# FPGA_LVDS.net
KiCad netlist of a schematic drawn in Altium Designer
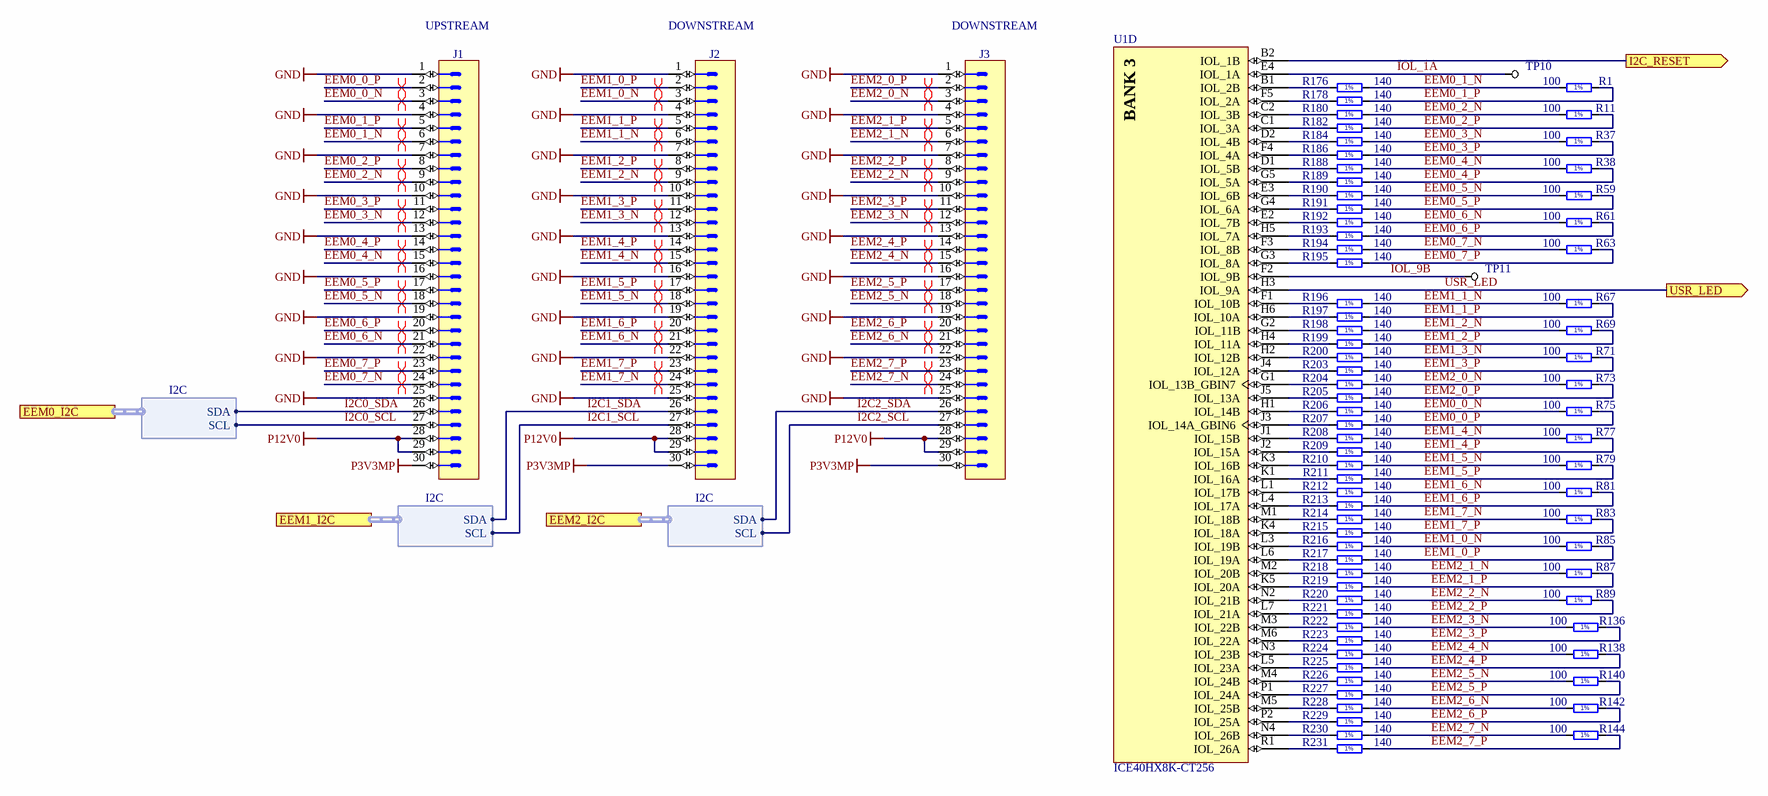
[diagram p0: FPGA_LVDS.SchDoc]

(export (version "E")
  (design (tool "Eeschema 10.0.6"))
  (components
    (comp (ref "J1")
      (value "~")
      (footprint "3M_N2530-6002RB")
      (description "Connector 30 Male")
      (fields
        (field (name "PART NUMBER") "3M_N2530-6002RB")
        (field (name "MANUFACTURER") "3M")
        (field (name "AUTHOR") "CERN DEM JLC")
      )
      (libsource (lib "Connectors") (part "Connector 30 Male"))
    )
    (comp (ref "J2")
      (value "~")
      (footprint "3M_N2530-6002RB")
      (description "Connector 30 Male")
      (fields
        (field (name "PART NUMBER") "3M_N2530-6002RB")
        (field (name "MANUFACTURER") "3M")
        (field (name "AUTHOR") "CERN DEM JLC")
      )
      (libsource (lib "Connectors") (part "Connector 30 Male"))
    )
    (comp (ref "J3")
      (value "~")
      (footprint "3M_N2530-6002RB")
      (description "Connector 30 Male")
      (fields
        (field (name "PART NUMBER") "3M_N2530-6002RB")
        (field (name "MANUFACTURER") "3M")
        (field (name "AUTHOR") "CERN DEM JLC")
      )
      (libsource (lib "Connectors") (part "Connector 30 Male"))
    )
    (comp (ref "R1")
      (value "100")
      (footprint "RESC1005X40N")
      (description "Resistor - 1%")
      (fields
        (field (name "PART NUMBER") "R0402_100R_1%_0.0625W_100PPM")
        (field (name "POWER") "0.0625W")
        (field (name "AUTHOR") "CERN DEM JLC")
      )
      (libsource (lib "Resistors") (part "Resistor - 1%"))
    )
    (comp (ref "R11")
      (value "100")
      (footprint "RESC1005X40N")
      (description "Resistor - 1%")
      (fields
        (field (name "PART NUMBER") "R0402_100R_1%_0.0625W_100PPM")
        (field (name "POWER") "0.0625W")
        (field (name "AUTHOR") "CERN DEM JLC")
      )
      (libsource (lib "Resistors") (part "Resistor - 1%"))
    )
    (comp (ref "R37")
      (value "100")
      (footprint "RESC1005X40N")
      (description "Resistor - 1%")
      (fields
        (field (name "PART NUMBER") "R0402_100R_1%_0.0625W_100PPM")
        (field (name "POWER") "0.0625W")
        (field (name "AUTHOR") "CERN DEM JLC")
      )
      (libsource (lib "Resistors") (part "Resistor - 1%"))
    )
    (comp (ref "R38")
      (value "100")
      (footprint "RESC1005X40N")
      (description "Resistor - 1%")
      (fields
        (field (name "PART NUMBER") "R0402_100R_1%_0.0625W_100PPM")
        (field (name "POWER") "0.0625W")
        (field (name "AUTHOR") "CERN DEM JLC")
      )
      (libsource (lib "Resistors") (part "Resistor - 1%"))
    )
    (comp (ref "R59")
      (value "100")
      (footprint "RESC1005X40N")
      (description "Resistor - 1%")
      (fields
        (field (name "PART NUMBER") "R0402_100R_1%_0.0625W_100PPM")
        (field (name "POWER") "0.0625W")
        (field (name "AUTHOR") "CERN DEM JLC")
      )
      (libsource (lib "Resistors") (part "Resistor - 1%"))
    )
    (comp (ref "R61")
      (value "100")
      (footprint "RESC1005X40N")
      (description "Resistor - 1%")
      (fields
        (field (name "PART NUMBER") "R0402_100R_1%_0.0625W_100PPM")
        (field (name "POWER") "0.0625W")
        (field (name "AUTHOR") "CERN DEM JLC")
      )
      (libsource (lib "Resistors") (part "Resistor - 1%"))
    )
    (comp (ref "R63")
      (value "100")
      (footprint "RESC1005X40N")
      (description "Resistor - 1%")
      (fields
        (field (name "PART NUMBER") "R0402_100R_1%_0.0625W_100PPM")
        (field (name "POWER") "0.0625W")
        (field (name "AUTHOR") "CERN DEM JLC")
      )
      (libsource (lib "Resistors") (part "Resistor - 1%"))
    )
    (comp (ref "R67")
      (value "100")
      (footprint "RESC1005X40N")
      (description "Resistor - 1%")
      (fields
        (field (name "PART NUMBER") "R0402_100R_1%_0.0625W_100PPM")
        (field (name "POWER") "0.0625W")
        (field (name "AUTHOR") "CERN DEM JLC")
      )
      (libsource (lib "Resistors") (part "Resistor - 1%"))
    )
    (comp (ref "R69")
      (value "100")
      (footprint "RESC1005X40N")
      (description "Resistor - 1%")
      (fields
        (field (name "PART NUMBER") "R0402_100R_1%_0.0625W_100PPM")
        (field (name "POWER") "0.0625W")
        (field (name "AUTHOR") "CERN DEM JLC")
      )
      (libsource (lib "Resistors") (part "Resistor - 1%"))
    )
    (comp (ref "R71")
      (value "100")
      (footprint "RESC1005X40N")
      (description "Resistor - 1%")
      (fields
        (field (name "PART NUMBER") "R0402_100R_1%_0.0625W_100PPM")
        (field (name "POWER") "0.0625W")
        (field (name "AUTHOR") "CERN DEM JLC")
      )
      (libsource (lib "Resistors") (part "Resistor - 1%"))
    )
    (comp (ref "R73")
      (value "100")
      (footprint "RESC1005X40N")
      (description "Resistor - 1%")
      (fields
        (field (name "PART NUMBER") "R0402_100R_1%_0.0625W_100PPM")
        (field (name "POWER") "0.0625W")
        (field (name "AUTHOR") "CERN DEM JLC")
      )
      (libsource (lib "Resistors") (part "Resistor - 1%"))
    )
    (comp (ref "R75")
      (value "100")
      (footprint "RESC1005X40N")
      (description "Resistor - 1%")
      (fields
        (field (name "PART NUMBER") "R0402_100R_1%_0.0625W_100PPM")
        (field (name "POWER") "0.0625W")
        (field (name "AUTHOR") "CERN DEM JLC")
      )
      (libsource (lib "Resistors") (part "Resistor - 1%"))
    )
    (comp (ref "R77")
      (value "100")
      (footprint "RESC1005X40N")
      (description "Resistor - 1%")
      (fields
        (field (name "PART NUMBER") "R0402_100R_1%_0.0625W_100PPM")
        (field (name "POWER") "0.0625W")
        (field (name "AUTHOR") "CERN DEM JLC")
      )
      (libsource (lib "Resistors") (part "Resistor - 1%"))
    )
    (comp (ref "R79")
      (value "100")
      (footprint "RESC1005X40N")
      (description "Resistor - 1%")
      (fields
        (field (name "PART NUMBER") "R0402_100R_1%_0.0625W_100PPM")
        (field (name "POWER") "0.0625W")
        (field (name "AUTHOR") "CERN DEM JLC")
      )
      (libsource (lib "Resistors") (part "Resistor - 1%"))
    )
    (comp (ref "R81")
      (value "100")
      (footprint "RESC1005X40N")
      (description "Resistor - 1%")
      (fields
        (field (name "PART NUMBER") "R0402_100R_1%_0.0625W_100PPM")
        (field (name "POWER") "0.0625W")
        (field (name "AUTHOR") "CERN DEM JLC")
      )
      (libsource (lib "Resistors") (part "Resistor - 1%"))
    )
    (comp (ref "R83")
      (value "100")
      (footprint "RESC1005X40N")
      (description "Resistor - 1%")
      (fields
        (field (name "PART NUMBER") "R0402_100R_1%_0.0625W_100PPM")
        (field (name "POWER") "0.0625W")
        (field (name "AUTHOR") "CERN DEM JLC")
      )
      (libsource (lib "Resistors") (part "Resistor - 1%"))
    )
    (comp (ref "R85")
      (value "100")
      (footprint "RESC1005X40N")
      (description "Resistor - 1%")
      (fields
        (field (name "PART NUMBER") "R0402_100R_1%_0.0625W_100PPM")
        (field (name "POWER") "0.0625W")
        (field (name "AUTHOR") "CERN DEM JLC")
      )
      (libsource (lib "Resistors") (part "Resistor - 1%"))
    )
    (comp (ref "R87")
      (value "100")
      (footprint "RESC1005X40N")
      (description "Resistor - 1%")
      (fields
        (field (name "PART NUMBER") "R0402_100R_1%_0.0625W_100PPM")
        (field (name "POWER") "0.0625W")
        (field (name "AUTHOR") "CERN DEM JLC")
      )
      (libsource (lib "Resistors") (part "Resistor - 1%"))
    )
    (comp (ref "R89")
      (value "100")
      (footprint "RESC1005X40N")
      (description "Resistor - 1%")
      (fields
        (field (name "PART NUMBER") "R0402_100R_1%_0.0625W_100PPM")
        (field (name "POWER") "0.0625W")
        (field (name "AUTHOR") "CERN DEM JLC")
      )
      (libsource (lib "Resistors") (part "Resistor - 1%"))
    )
    (comp (ref "R136")
      (value "100")
      (footprint "RESC1005X40N")
      (description "Resistor - 1%")
      (fields
        (field (name "PART NUMBER") "R0402_100R_1%_0.0625W_100PPM")
        (field (name "POWER") "0.0625W")
        (field (name "AUTHOR") "CERN DEM JLC")
      )
      (libsource (lib "Resistors") (part "Resistor - 1%"))
    )
    (comp (ref "R138")
      (value "100")
      (footprint "RESC1005X40N")
      (description "Resistor - 1%")
      (fields
        (field (name "PART NUMBER") "R0402_100R_1%_0.0625W_100PPM")
        (field (name "POWER") "0.0625W")
        (field (name "AUTHOR") "CERN DEM JLC")
      )
      (libsource (lib "Resistors") (part "Resistor - 1%"))
    )
    (comp (ref "R140")
      (value "100")
      (footprint "RESC1005X40N")
      (description "Resistor - 1%")
      (fields
        (field (name "PART NUMBER") "R0402_100R_1%_0.0625W_100PPM")
        (field (name "POWER") "0.0625W")
        (field (name "AUTHOR") "CERN DEM JLC")
      )
      (libsource (lib "Resistors") (part "Resistor - 1%"))
    )
    (comp (ref "R142")
      (value "100")
      (footprint "RESC1005X40N")
      (description "Resistor - 1%")
      (fields
        (field (name "PART NUMBER") "R0402_100R_1%_0.0625W_100PPM")
        (field (name "POWER") "0.0625W")
        (field (name "AUTHOR") "CERN DEM JLC")
      )
      (libsource (lib "Resistors") (part "Resistor - 1%"))
    )
    (comp (ref "R144")
      (value "100")
      (footprint "RESC1005X40N")
      (description "Resistor - 1%")
      (fields
        (field (name "PART NUMBER") "R0402_100R_1%_0.0625W_100PPM")
        (field (name "POWER") "0.0625W")
        (field (name "AUTHOR") "CERN DEM JLC")
      )
      (libsource (lib "Resistors") (part "Resistor - 1%"))
    )
    (comp (ref "R176")
      (value "140")
      (footprint "RESC0603X28N")
      (description "Resistor - 1%")
      (fields
        (field (name "PART NUMBER") "R0201_140R_1%_0.05W_200PPM")
        (field (name "POWER") "0.05W")
        (field (name "AUTHOR") "CERN DEM MR")
      )
      (libsource (lib "Resistors") (part "Resistor - 1%"))
    )
    (comp (ref "R178")
      (value "140")
      (footprint "RESC0603X28N")
      (description "Resistor - 1%")
      (fields
        (field (name "PART NUMBER") "R0201_140R_1%_0.05W_200PPM")
        (field (name "POWER") "0.05W")
        (field (name "AUTHOR") "CERN DEM MR")
      )
      (libsource (lib "Resistors") (part "Resistor - 1%"))
    )
    (comp (ref "R180")
      (value "140")
      (footprint "RESC0603X28N")
      (description "Resistor - 1%")
      (fields
        (field (name "PART NUMBER") "R0201_140R_1%_0.05W_200PPM")
        (field (name "POWER") "0.05W")
        (field (name "AUTHOR") "CERN DEM MR")
      )
      (libsource (lib "Resistors") (part "Resistor - 1%"))
    )
    (comp (ref "R182")
      (value "140")
      (footprint "RESC0603X28N")
      (description "Resistor - 1%")
      (fields
        (field (name "PART NUMBER") "R0201_140R_1%_0.05W_200PPM")
        (field (name "POWER") "0.05W")
        (field (name "AUTHOR") "CERN DEM MR")
      )
      (libsource (lib "Resistors") (part "Resistor - 1%"))
    )
    (comp (ref "R184")
      (value "140")
      (footprint "RESC0603X28N")
      (description "Resistor - 1%")
      (fields
        (field (name "PART NUMBER") "R0201_140R_1%_0.05W_200PPM")
        (field (name "POWER") "0.05W")
        (field (name "AUTHOR") "CERN DEM MR")
      )
      (libsource (lib "Resistors") (part "Resistor - 1%"))
    )
    (comp (ref "R186")
      (value "140")
      (footprint "RESC0603X28N")
      (description "Resistor - 1%")
      (fields
        (field (name "PART NUMBER") "R0201_140R_1%_0.05W_200PPM")
        (field (name "POWER") "0.05W")
        (field (name "AUTHOR") "CERN DEM MR")
      )
      (libsource (lib "Resistors") (part "Resistor - 1%"))
    )
    (comp (ref "R188")
      (value "140")
      (footprint "RESC0603X28N")
      (description "Resistor - 1%")
      (fields
        (field (name "PART NUMBER") "R0201_140R_1%_0.05W_200PPM")
        (field (name "POWER") "0.05W")
        (field (name "AUTHOR") "CERN DEM MR")
      )
      (libsource (lib "Resistors") (part "Resistor - 1%"))
    )
    (comp (ref "R189")
      (value "140")
      (footprint "RESC0603X28N")
      (description "Resistor - 1%")
      (fields
        (field (name "PART NUMBER") "R0201_140R_1%_0.05W_200PPM")
        (field (name "POWER") "0.05W")
        (field (name "AUTHOR") "CERN DEM MR")
      )
      (libsource (lib "Resistors") (part "Resistor - 1%"))
    )
    (comp (ref "R190")
      (value "140")
      (footprint "RESC0603X28N")
      (description "Resistor - 1%")
      (fields
        (field (name "PART NUMBER") "R0201_140R_1%_0.05W_200PPM")
        (field (name "POWER") "0.05W")
        (field (name "AUTHOR") "CERN DEM MR")
      )
      (libsource (lib "Resistors") (part "Resistor - 1%"))
    )
    (comp (ref "R191")
      (value "140")
      (footprint "RESC0603X28N")
      (description "Resistor - 1%")
      (fields
        (field (name "PART NUMBER") "R0201_140R_1%_0.05W_200PPM")
        (field (name "POWER") "0.05W")
        (field (name "AUTHOR") "CERN DEM MR")
      )
      (libsource (lib "Resistors") (part "Resistor - 1%"))
    )
    (comp (ref "R192")
      (value "140")
      (footprint "RESC0603X28N")
      (description "Resistor - 1%")
      (fields
        (field (name "PART NUMBER") "R0201_140R_1%_0.05W_200PPM")
        (field (name "POWER") "0.05W")
        (field (name "AUTHOR") "CERN DEM MR")
      )
      (libsource (lib "Resistors") (part "Resistor - 1%"))
    )
    (comp (ref "R193")
      (value "140")
      (footprint "RESC0603X28N")
      (description "Resistor - 1%")
      (fields
        (field (name "PART NUMBER") "R0201_140R_1%_0.05W_200PPM")
        (field (name "POWER") "0.05W")
        (field (name "AUTHOR") "CERN DEM MR")
      )
      (libsource (lib "Resistors") (part "Resistor - 1%"))
    )
    (comp (ref "R194")
      (value "140")
      (footprint "RESC0603X28N")
      (description "Resistor - 1%")
      (fields
        (field (name "PART NUMBER") "R0201_140R_1%_0.05W_200PPM")
        (field (name "POWER") "0.05W")
        (field (name "AUTHOR") "CERN DEM MR")
      )
      (libsource (lib "Resistors") (part "Resistor - 1%"))
    )
    (comp (ref "R195")
      (value "140")
      (footprint "RESC0603X28N")
      (description "Resistor - 1%")
      (fields
        (field (name "PART NUMBER") "R0201_140R_1%_0.05W_200PPM")
        (field (name "POWER") "0.05W")
        (field (name "AUTHOR") "CERN DEM MR")
      )
      (libsource (lib "Resistors") (part "Resistor - 1%"))
    )
    (comp (ref "R196")
      (value "140")
      (footprint "RESC0603X28N")
      (description "Resistor - 1%")
      (fields
        (field (name "PART NUMBER") "R0201_140R_1%_0.05W_200PPM")
        (field (name "POWER") "0.05W")
        (field (name "AUTHOR") "CERN DEM MR")
      )
      (libsource (lib "Resistors") (part "Resistor - 1%"))
    )
    (comp (ref "R197")
      (value "140")
      (footprint "RESC0603X28N")
      (description "Resistor - 1%")
      (fields
        (field (name "PART NUMBER") "R0201_140R_1%_0.05W_200PPM")
        (field (name "POWER") "0.05W")
        (field (name "AUTHOR") "CERN DEM MR")
      )
      (libsource (lib "Resistors") (part "Resistor - 1%"))
    )
    (comp (ref "R198")
      (value "140")
      (footprint "RESC0603X28N")
      (description "Resistor - 1%")
      (fields
        (field (name "PART NUMBER") "R0201_140R_1%_0.05W_200PPM")
        (field (name "POWER") "0.05W")
        (field (name "AUTHOR") "CERN DEM MR")
      )
      (libsource (lib "Resistors") (part "Resistor - 1%"))
    )
    (comp (ref "R199")
      (value "140")
      (footprint "RESC0603X28N")
      (description "Resistor - 1%")
      (fields
        (field (name "PART NUMBER") "R0201_140R_1%_0.05W_200PPM")
        (field (name "POWER") "0.05W")
        (field (name "AUTHOR") "CERN DEM MR")
      )
      (libsource (lib "Resistors") (part "Resistor - 1%"))
    )
    (comp (ref "R200")
      (value "140")
      (footprint "RESC0603X28N")
      (description "Resistor - 1%")
      (fields
        (field (name "PART NUMBER") "R0201_140R_1%_0.05W_200PPM")
        (field (name "POWER") "0.05W")
        (field (name "AUTHOR") "CERN DEM MR")
      )
      (libsource (lib "Resistors") (part "Resistor - 1%"))
    )
    (comp (ref "R203")
      (value "140")
      (footprint "RESC0603X28N")
      (description "Resistor - 1%")
      (fields
        (field (name "PART NUMBER") "R0201_140R_1%_0.05W_200PPM")
        (field (name "POWER") "0.05W")
        (field (name "AUTHOR") "CERN DEM MR")
      )
      (libsource (lib "Resistors") (part "Resistor - 1%"))
    )
    (comp (ref "R204")
      (value "140")
      (footprint "RESC0603X28N")
      (description "Resistor - 1%")
      (fields
        (field (name "PART NUMBER") "R0201_140R_1%_0.05W_200PPM")
        (field (name "POWER") "0.05W")
        (field (name "AUTHOR") "CERN DEM MR")
      )
      (libsource (lib "Resistors") (part "Resistor - 1%"))
    )
    (comp (ref "R205")
      (value "140")
      (footprint "RESC0603X28N")
      (description "Resistor - 1%")
      (fields
        (field (name "PART NUMBER") "R0201_140R_1%_0.05W_200PPM")
        (field (name "POWER") "0.05W")
        (field (name "AUTHOR") "CERN DEM MR")
      )
      (libsource (lib "Resistors") (part "Resistor - 1%"))
    )
    (comp (ref "R206")
      (value "140")
      (footprint "RESC0603X28N")
      (description "Resistor - 1%")
      (fields
        (field (name "PART NUMBER") "R0201_140R_1%_0.05W_200PPM")
        (field (name "POWER") "0.05W")
        (field (name "AUTHOR") "CERN DEM MR")
      )
      (libsource (lib "Resistors") (part "Resistor - 1%"))
    )
    (comp (ref "R207")
      (value "140")
      (footprint "RESC0603X28N")
      (description "Resistor - 1%")
      (fields
        (field (name "PART NUMBER") "R0201_140R_1%_0.05W_200PPM")
        (field (name "POWER") "0.05W")
        (field (name "AUTHOR") "CERN DEM MR")
      )
      (libsource (lib "Resistors") (part "Resistor - 1%"))
    )
    (comp (ref "R208")
      (value "140")
      (footprint "RESC0603X28N")
      (description "Resistor - 1%")
      (fields
        (field (name "PART NUMBER") "R0201_140R_1%_0.05W_200PPM")
        (field (name "POWER") "0.05W")
        (field (name "AUTHOR") "CERN DEM MR")
      )
      (libsource (lib "Resistors") (part "Resistor - 1%"))
    )
    (comp (ref "R209")
      (value "140")
      (footprint "RESC0603X28N")
      (description "Resistor - 1%")
      (fields
        (field (name "PART NUMBER") "R0201_140R_1%_0.05W_200PPM")
        (field (name "POWER") "0.05W")
        (field (name "AUTHOR") "CERN DEM MR")
      )
      (libsource (lib "Resistors") (part "Resistor - 1%"))
    )
    (comp (ref "R210")
      (value "140")
      (footprint "RESC0603X28N")
      (description "Resistor - 1%")
      (fields
        (field (name "PART NUMBER") "R0201_140R_1%_0.05W_200PPM")
        (field (name "POWER") "0.05W")
        (field (name "AUTHOR") "CERN DEM MR")
      )
      (libsource (lib "Resistors") (part "Resistor - 1%"))
    )
    (comp (ref "R211")
      (value "140")
      (footprint "RESC0603X28N")
      (description "Resistor - 1%")
      (fields
        (field (name "PART NUMBER") "R0201_140R_1%_0.05W_200PPM")
        (field (name "POWER") "0.05W")
        (field (name "AUTHOR") "CERN DEM MR")
      )
      (libsource (lib "Resistors") (part "Resistor - 1%"))
    )
    (comp (ref "R212")
      (value "140")
      (footprint "RESC0603X28N")
      (description "Resistor - 1%")
      (fields
        (field (name "PART NUMBER") "R0201_140R_1%_0.05W_200PPM")
        (field (name "POWER") "0.05W")
        (field (name "AUTHOR") "CERN DEM MR")
      )
      (libsource (lib "Resistors") (part "Resistor - 1%"))
    )
    (comp (ref "R213")
      (value "140")
      (footprint "RESC0603X28N")
      (description "Resistor - 1%")
      (fields
        (field (name "PART NUMBER") "R0201_140R_1%_0.05W_200PPM")
        (field (name "POWER") "0.05W")
        (field (name "AUTHOR") "CERN DEM MR")
      )
      (libsource (lib "Resistors") (part "Resistor - 1%"))
    )
    (comp (ref "R214")
      (value "140")
      (footprint "RESC0603X28N")
      (description "Resistor - 1%")
      (fields
        (field (name "PART NUMBER") "R0201_140R_1%_0.05W_200PPM")
        (field (name "POWER") "0.05W")
        (field (name "AUTHOR") "CERN DEM MR")
      )
      (libsource (lib "Resistors") (part "Resistor - 1%"))
    )
    (comp (ref "R215")
      (value "140")
      (footprint "RESC0603X28N")
      (description "Resistor - 1%")
      (fields
        (field (name "PART NUMBER") "R0201_140R_1%_0.05W_200PPM")
        (field (name "POWER") "0.05W")
        (field (name "AUTHOR") "CERN DEM MR")
      )
      (libsource (lib "Resistors") (part "Resistor - 1%"))
    )
    (comp (ref "R216")
      (value "140")
      (footprint "RESC0603X28N")
      (description "Resistor - 1%")
      (fields
        (field (name "PART NUMBER") "R0201_140R_1%_0.05W_200PPM")
        (field (name "POWER") "0.05W")
        (field (name "AUTHOR") "CERN DEM MR")
      )
      (libsource (lib "Resistors") (part "Resistor - 1%"))
    )
    (comp (ref "R217")
      (value "140")
      (footprint "RESC0603X28N")
      (description "Resistor - 1%")
      (fields
        (field (name "PART NUMBER") "R0201_140R_1%_0.05W_200PPM")
        (field (name "POWER") "0.05W")
        (field (name "AUTHOR") "CERN DEM MR")
      )
      (libsource (lib "Resistors") (part "Resistor - 1%"))
    )
    (comp (ref "R218")
      (value "140")
      (footprint "RESC0603X28N")
      (description "Resistor - 1%")
      (fields
        (field (name "PART NUMBER") "R0201_140R_1%_0.05W_200PPM")
        (field (name "POWER") "0.05W")
        (field (name "AUTHOR") "CERN DEM MR")
      )
      (libsource (lib "Resistors") (part "Resistor - 1%"))
    )
    (comp (ref "R219")
      (value "140")
      (footprint "RESC0603X28N")
      (description "Resistor - 1%")
      (fields
        (field (name "PART NUMBER") "R0201_140R_1%_0.05W_200PPM")
        (field (name "POWER") "0.05W")
        (field (name "AUTHOR") "CERN DEM MR")
      )
      (libsource (lib "Resistors") (part "Resistor - 1%"))
    )
    (comp (ref "R220")
      (value "140")
      (footprint "RESC0603X28N")
      (description "Resistor - 1%")
      (fields
        (field (name "PART NUMBER") "R0201_140R_1%_0.05W_200PPM")
        (field (name "POWER") "0.05W")
        (field (name "AUTHOR") "CERN DEM MR")
      )
      (libsource (lib "Resistors") (part "Resistor - 1%"))
    )
    (comp (ref "R221")
      (value "140")
      (footprint "RESC0603X28N")
      (description "Resistor - 1%")
      (fields
        (field (name "PART NUMBER") "R0201_140R_1%_0.05W_200PPM")
        (field (name "POWER") "0.05W")
        (field (name "AUTHOR") "CERN DEM MR")
      )
      (libsource (lib "Resistors") (part "Resistor - 1%"))
    )
    (comp (ref "R222")
      (value "140")
      (footprint "RESC0603X28N")
      (description "Resistor - 1%")
      (fields
        (field (name "PART NUMBER") "R0201_140R_1%_0.05W_200PPM")
        (field (name "POWER") "0.05W")
        (field (name "AUTHOR") "CERN DEM MR")
      )
      (libsource (lib "Resistors") (part "Resistor - 1%"))
    )
    (comp (ref "R223")
      (value "140")
      (footprint "RESC0603X28N")
      (description "Resistor - 1%")
      (fields
        (field (name "PART NUMBER") "R0201_140R_1%_0.05W_200PPM")
        (field (name "POWER") "0.05W")
        (field (name "AUTHOR") "CERN DEM MR")
      )
      (libsource (lib "Resistors") (part "Resistor - 1%"))
    )
    (comp (ref "R224")
      (value "140")
      (footprint "RESC0603X28N")
      (description "Resistor - 1%")
      (fields
        (field (name "PART NUMBER") "R0201_140R_1%_0.05W_200PPM")
        (field (name "POWER") "0.05W")
        (field (name "AUTHOR") "CERN DEM MR")
      )
      (libsource (lib "Resistors") (part "Resistor - 1%"))
    )
    (comp (ref "R225")
      (value "140")
      (footprint "RESC0603X28N")
      (description "Resistor - 1%")
      (fields
        (field (name "PART NUMBER") "R0201_140R_1%_0.05W_200PPM")
        (field (name "POWER") "0.05W")
        (field (name "AUTHOR") "CERN DEM MR")
      )
      (libsource (lib "Resistors") (part "Resistor - 1%"))
    )
    (comp (ref "R226")
      (value "140")
      (footprint "RESC0603X28N")
      (description "Resistor - 1%")
      (fields
        (field (name "PART NUMBER") "R0201_140R_1%_0.05W_200PPM")
        (field (name "POWER") "0.05W")
        (field (name "AUTHOR") "CERN DEM MR")
      )
      (libsource (lib "Resistors") (part "Resistor - 1%"))
    )
    (comp (ref "R227")
      (value "140")
      (footprint "RESC0603X28N")
      (description "Resistor - 1%")
      (fields
        (field (name "PART NUMBER") "R0201_140R_1%_0.05W_200PPM")
        (field (name "POWER") "0.05W")
        (field (name "AUTHOR") "CERN DEM MR")
      )
      (libsource (lib "Resistors") (part "Resistor - 1%"))
    )
    (comp (ref "R228")
      (value "140")
      (footprint "RESC0603X28N")
      (description "Resistor - 1%")
      (fields
        (field (name "PART NUMBER") "R0201_140R_1%_0.05W_200PPM")
        (field (name "POWER") "0.05W")
        (field (name "AUTHOR") "CERN DEM MR")
      )
      (libsource (lib "Resistors") (part "Resistor - 1%"))
    )
    (comp (ref "R229")
      (value "140")
      (footprint "RESC0603X28N")
      (description "Resistor - 1%")
      (fields
        (field (name "PART NUMBER") "R0201_140R_1%_0.05W_200PPM")
        (field (name "POWER") "0.05W")
        (field (name "AUTHOR") "CERN DEM MR")
      )
      (libsource (lib "Resistors") (part "Resistor - 1%"))
    )
    (comp (ref "R230")
      (value "140")
      (footprint "RESC0603X28N")
      (description "Resistor - 1%")
      (fields
        (field (name "PART NUMBER") "R0201_140R_1%_0.05W_200PPM")
        (field (name "POWER") "0.05W")
        (field (name "AUTHOR") "CERN DEM MR")
      )
      (libsource (lib "Resistors") (part "Resistor - 1%"))
    )
    (comp (ref "R231")
      (value "140")
      (footprint "RESC0603X28N")
      (description "Resistor - 1%")
      (fields
        (field (name "PART NUMBER") "R0201_140R_1%_0.05W_200PPM")
        (field (name "POWER") "0.05W")
        (field (name "AUTHOR") "CERN DEM MR")
      )
      (libsource (lib "Resistors") (part "Resistor - 1%"))
    )
    (comp (ref "TP10")
      (value "TP")
      (footprint "TP")
      (description "Testpoint")
      (libsource (lib "LIBRARY_SCH") (part "TP"))
    )
    (comp (ref "TP11")
      (value "TP")
      (footprint "TP")
      (description "Testpoint")
      (libsource (lib "LIBRARY_SCH") (part "TP"))
    )
    (comp (ref "U1")
      (value "ICE40HX8K-CT256")
      (footprint "LATC-caBGA-256")
      (fields (field (name "MANUFACTURER") "Lattice Semiconductor"))
      (libsource (lib "Altium Content Vault") (part "LATC-HX8K-caBGA-256"))
    )
  )
  (nets
    (net (code "2") (name "/EEM0_0_N") (class "Default")
      (node (ref "J1") (pin "3") (pinfunction "3_3") (pintype "bidirectional"))
      (node (ref "R206") (pin "2") (pinfunction "2_2") (pintype "passive"))
      (node (ref "R75") (pin "1") (pinfunction "1_1") (pintype "passive"))
    )
    (net (code "3") (name "/EEM0_0_P") (class "Default")
      (node (ref "J1") (pin "2") (pinfunction "2_2") (pintype "bidirectional"))
      (node (ref "R207") (pin "2") (pinfunction "2_2") (pintype "passive"))
      (node (ref "R75") (pin "2") (pinfunction "2_2") (pintype "passive"))
    )
    (net (code "4") (name "/EEM0_1_N") (class "Default")
      (node (ref "J1") (pin "6") (pinfunction "6_6") (pintype "bidirectional"))
      (node (ref "R1") (pin "1") (pinfunction "1_1") (pintype "passive"))
      (node (ref "R176") (pin "2") (pinfunction "2_2") (pintype "passive"))
    )
    (net (code "5") (name "/EEM0_1_P") (class "Default")
      (node (ref "J1") (pin "5") (pinfunction "5_5") (pintype "bidirectional"))
      (node (ref "R1") (pin "2") (pinfunction "2_2") (pintype "passive"))
      (node (ref "R178") (pin "2") (pinfunction "2_2") (pintype "passive"))
    )
    (net (code "6") (name "/EEM0_2_N") (class "Default")
      (node (ref "J1") (pin "9") (pinfunction "9_9") (pintype "bidirectional"))
      (node (ref "R11") (pin "1") (pinfunction "1_1") (pintype "passive"))
      (node (ref "R180") (pin "2") (pinfunction "2_2") (pintype "passive"))
    )
    (net (code "7") (name "/EEM0_2_P") (class "Default")
      (node (ref "J1") (pin "8") (pinfunction "8_8") (pintype "bidirectional"))
      (node (ref "R11") (pin "2") (pinfunction "2_2") (pintype "passive"))
      (node (ref "R182") (pin "2") (pinfunction "2_2") (pintype "passive"))
    )
    (net (code "8") (name "/EEM0_3_N") (class "Default")
      (node (ref "J1") (pin "12") (pinfunction "12_12") (pintype "bidirectional"))
      (node (ref "R184") (pin "2") (pinfunction "2_2") (pintype "passive"))
      (node (ref "R37") (pin "1") (pinfunction "1_1") (pintype "passive"))
    )
    (net (code "9") (name "/EEM0_3_P") (class "Default")
      (node (ref "J1") (pin "11") (pinfunction "11_11") (pintype "bidirectional"))
      (node (ref "R186") (pin "2") (pinfunction "2_2") (pintype "passive"))
      (node (ref "R37") (pin "2") (pinfunction "2_2") (pintype "passive"))
    )
    (net (code "10") (name "/EEM0_4_N") (class "Default")
      (node (ref "J1") (pin "15") (pinfunction "15_15") (pintype "bidirectional"))
      (node (ref "R188") (pin "2") (pinfunction "2_2") (pintype "passive"))
      (node (ref "R38") (pin "1") (pinfunction "1_1") (pintype "passive"))
    )
    (net (code "11") (name "/EEM0_4_P") (class "Default")
      (node (ref "J1") (pin "14") (pinfunction "14_14") (pintype "bidirectional"))
      (node (ref "R189") (pin "2") (pinfunction "2_2") (pintype "passive"))
      (node (ref "R38") (pin "2") (pinfunction "2_2") (pintype "passive"))
    )
    (net (code "12") (name "/EEM0_5_N") (class "Default")
      (node (ref "J1") (pin "18") (pinfunction "18_18") (pintype "bidirectional"))
      (node (ref "R190") (pin "2") (pinfunction "2_2") (pintype "passive"))
      (node (ref "R59") (pin "1") (pinfunction "1_1") (pintype "passive"))
    )
    (net (code "13") (name "/EEM0_5_P") (class "Default")
      (node (ref "J1") (pin "17") (pinfunction "17_17") (pintype "bidirectional"))
      (node (ref "R191") (pin "2") (pinfunction "2_2") (pintype "passive"))
      (node (ref "R59") (pin "2") (pinfunction "2_2") (pintype "passive"))
    )
    (net (code "14") (name "/EEM0_6_N") (class "Default")
      (node (ref "J1") (pin "21") (pinfunction "21_21") (pintype "bidirectional"))
      (node (ref "R192") (pin "2") (pinfunction "2_2") (pintype "passive"))
      (node (ref "R61") (pin "1") (pinfunction "1_1") (pintype "passive"))
    )
    (net (code "15") (name "/EEM0_6_P") (class "Default")
      (node (ref "J1") (pin "20") (pinfunction "20_20") (pintype "bidirectional"))
      (node (ref "R193") (pin "2") (pinfunction "2_2") (pintype "passive"))
      (node (ref "R61") (pin "2") (pinfunction "2_2") (pintype "passive"))
    )
    (net (code "16") (name "/EEM0_7_N") (class "Default")
      (node (ref "J1") (pin "24") (pinfunction "24_24") (pintype "bidirectional"))
      (node (ref "R194") (pin "2") (pinfunction "2_2") (pintype "passive"))
      (node (ref "R63") (pin "1") (pinfunction "1_1") (pintype "passive"))
    )
    (net (code "17") (name "/EEM0_7_P") (class "Default")
      (node (ref "J1") (pin "23") (pinfunction "23_23") (pintype "bidirectional"))
      (node (ref "R195") (pin "2") (pinfunction "2_2") (pintype "passive"))
      (node (ref "R63") (pin "2") (pinfunction "2_2") (pintype "passive"))
    )
    (net (code "18") (name "/EEM1_0_N") (class "Default")
      (node (ref "J2") (pin "3") (pinfunction "3_3") (pintype "bidirectional"))
      (node (ref "R216") (pin "2") (pinfunction "2_2") (pintype "passive"))
      (node (ref "R85") (pin "1") (pinfunction "1_1") (pintype "passive"))
    )
    (net (code "19") (name "/EEM1_0_P") (class "Default")
      (node (ref "J2") (pin "2") (pinfunction "2_2") (pintype "bidirectional"))
      (node (ref "R217") (pin "2") (pinfunction "2_2") (pintype "passive"))
      (node (ref "R85") (pin "2") (pinfunction "2_2") (pintype "passive"))
    )
    (net (code "20") (name "/EEM1_1_N") (class "Default")
      (node (ref "J2") (pin "6") (pinfunction "6_6") (pintype "bidirectional"))
      (node (ref "R196") (pin "2") (pinfunction "2_2") (pintype "passive"))
      (node (ref "R67") (pin "1") (pinfunction "1_1") (pintype "passive"))
    )
    (net (code "21") (name "/EEM1_1_P") (class "Default")
      (node (ref "J2") (pin "5") (pinfunction "5_5") (pintype "bidirectional"))
      (node (ref "R197") (pin "2") (pinfunction "2_2") (pintype "passive"))
      (node (ref "R67") (pin "2") (pinfunction "2_2") (pintype "passive"))
    )
    (net (code "22") (name "/EEM1_2_N") (class "Default")
      (node (ref "J2") (pin "9") (pinfunction "9_9") (pintype "bidirectional"))
      (node (ref "R198") (pin "2") (pinfunction "2_2") (pintype "passive"))
      (node (ref "R69") (pin "1") (pinfunction "1_1") (pintype "passive"))
    )
    (net (code "23") (name "/EEM1_2_P") (class "Default")
      (node (ref "J2") (pin "8") (pinfunction "8_8") (pintype "bidirectional"))
      (node (ref "R199") (pin "2") (pinfunction "2_2") (pintype "passive"))
      (node (ref "R69") (pin "2") (pinfunction "2_2") (pintype "passive"))
    )
    (net (code "24") (name "/EEM1_3_N") (class "Default")
      (node (ref "J2") (pin "12") (pinfunction "12_12") (pintype "bidirectional"))
      (node (ref "R200") (pin "2") (pinfunction "2_2") (pintype "passive"))
      (node (ref "R71") (pin "1") (pinfunction "1_1") (pintype "passive"))
    )
    (net (code "25") (name "/EEM1_3_P") (class "Default")
      (node (ref "J2") (pin "11") (pinfunction "11_11") (pintype "bidirectional"))
      (node (ref "R203") (pin "2") (pinfunction "2_2") (pintype "passive"))
      (node (ref "R71") (pin "2") (pinfunction "2_2") (pintype "passive"))
    )
    (net (code "26") (name "/EEM1_4_N") (class "Default")
      (node (ref "J2") (pin "15") (pinfunction "15_15") (pintype "bidirectional"))
      (node (ref "R208") (pin "2") (pinfunction "2_2") (pintype "passive"))
      (node (ref "R77") (pin "1") (pinfunction "1_1") (pintype "passive"))
    )
    (net (code "27") (name "/EEM1_4_P") (class "Default")
      (node (ref "J2") (pin "14") (pinfunction "14_14") (pintype "bidirectional"))
      (node (ref "R209") (pin "2") (pinfunction "2_2") (pintype "passive"))
      (node (ref "R77") (pin "2") (pinfunction "2_2") (pintype "passive"))
    )
    (net (code "28") (name "/EEM1_5_N") (class "Default")
      (node (ref "J2") (pin "18") (pinfunction "18_18") (pintype "bidirectional"))
      (node (ref "R210") (pin "2") (pinfunction "2_2") (pintype "passive"))
      (node (ref "R79") (pin "1") (pinfunction "1_1") (pintype "passive"))
    )
    (net (code "29") (name "/EEM1_5_P") (class "Default")
      (node (ref "J2") (pin "17") (pinfunction "17_17") (pintype "bidirectional"))
      (node (ref "R211") (pin "2") (pinfunction "2_2") (pintype "passive"))
      (node (ref "R79") (pin "2") (pinfunction "2_2") (pintype "passive"))
    )
    (net (code "30") (name "/EEM1_6_N") (class "Default")
      (node (ref "J2") (pin "21") (pinfunction "21_21") (pintype "bidirectional"))
      (node (ref "R212") (pin "2") (pinfunction "2_2") (pintype "passive"))
      (node (ref "R81") (pin "1") (pinfunction "1_1") (pintype "passive"))
    )
    (net (code "31") (name "/EEM1_6_P") (class "Default")
      (node (ref "J2") (pin "20") (pinfunction "20_20") (pintype "bidirectional"))
      (node (ref "R213") (pin "2") (pinfunction "2_2") (pintype "passive"))
      (node (ref "R81") (pin "2") (pinfunction "2_2") (pintype "passive"))
    )
    (net (code "32") (name "/EEM1_7_N") (class "Default")
      (node (ref "J2") (pin "24") (pinfunction "24_24") (pintype "bidirectional"))
      (node (ref "R214") (pin "2") (pinfunction "2_2") (pintype "passive"))
      (node (ref "R83") (pin "1") (pinfunction "1_1") (pintype "passive"))
    )
    (net (code "33") (name "/EEM1_7_P") (class "Default")
      (node (ref "J2") (pin "23") (pinfunction "23_23") (pintype "bidirectional"))
      (node (ref "R215") (pin "2") (pinfunction "2_2") (pintype "passive"))
      (node (ref "R83") (pin "2") (pinfunction "2_2") (pintype "passive"))
    )
    (net (code "34") (name "/EEM2_0_N") (class "Default")
      (node (ref "J3") (pin "3") (pinfunction "3_3") (pintype "bidirectional"))
      (node (ref "R204") (pin "2") (pinfunction "2_2") (pintype "passive"))
      (node (ref "R73") (pin "1") (pinfunction "1_1") (pintype "passive"))
    )
    (net (code "35") (name "/EEM2_0_P") (class "Default")
      (node (ref "J3") (pin "2") (pinfunction "2_2") (pintype "bidirectional"))
      (node (ref "R205") (pin "2") (pinfunction "2_2") (pintype "passive"))
      (node (ref "R73") (pin "2") (pinfunction "2_2") (pintype "passive"))
    )
    (net (code "36") (name "/EEM2_1_N") (class "Default")
      (node (ref "J3") (pin "6") (pinfunction "6_6") (pintype "bidirectional"))
      (node (ref "R218") (pin "2") (pinfunction "2_2") (pintype "passive"))
      (node (ref "R87") (pin "1") (pinfunction "1_1") (pintype "passive"))
    )
    (net (code "37") (name "/EEM2_1_P") (class "Default")
      (node (ref "J3") (pin "5") (pinfunction "5_5") (pintype "bidirectional"))
      (node (ref "R219") (pin "2") (pinfunction "2_2") (pintype "passive"))
      (node (ref "R87") (pin "2") (pinfunction "2_2") (pintype "passive"))
    )
    (net (code "38") (name "/EEM2_2_N") (class "Default")
      (node (ref "J3") (pin "9") (pinfunction "9_9") (pintype "bidirectional"))
      (node (ref "R220") (pin "2") (pinfunction "2_2") (pintype "passive"))
      (node (ref "R89") (pin "1") (pinfunction "1_1") (pintype "passive"))
    )
    (net (code "39") (name "/EEM2_2_P") (class "Default")
      (node (ref "J3") (pin "8") (pinfunction "8_8") (pintype "bidirectional"))
      (node (ref "R221") (pin "2") (pinfunction "2_2") (pintype "passive"))
      (node (ref "R89") (pin "2") (pinfunction "2_2") (pintype "passive"))
    )
    (net (code "40") (name "/EEM2_3_N") (class "Default")
      (node (ref "J3") (pin "12") (pinfunction "12_12") (pintype "bidirectional"))
      (node (ref "R136") (pin "1") (pinfunction "1_1") (pintype "passive"))
      (node (ref "R222") (pin "2") (pinfunction "2_2") (pintype "passive"))
    )
    (net (code "41") (name "/EEM2_3_P") (class "Default")
      (node (ref "J3") (pin "11") (pinfunction "11_11") (pintype "bidirectional"))
      (node (ref "R136") (pin "2") (pinfunction "2_2") (pintype "passive"))
      (node (ref "R223") (pin "2") (pinfunction "2_2") (pintype "passive"))
    )
    (net (code "42") (name "/EEM2_4_N") (class "Default")
      (node (ref "J3") (pin "15") (pinfunction "15_15") (pintype "bidirectional"))
      (node (ref "R138") (pin "1") (pinfunction "1_1") (pintype "passive"))
      (node (ref "R224") (pin "2") (pinfunction "2_2") (pintype "passive"))
    )
    (net (code "43") (name "/EEM2_4_P") (class "Default")
      (node (ref "J3") (pin "14") (pinfunction "14_14") (pintype "bidirectional"))
      (node (ref "R138") (pin "2") (pinfunction "2_2") (pintype "passive"))
      (node (ref "R225") (pin "2") (pinfunction "2_2") (pintype "passive"))
    )
    (net (code "44") (name "/EEM2_5_N") (class "Default")
      (node (ref "J3") (pin "18") (pinfunction "18_18") (pintype "bidirectional"))
      (node (ref "R140") (pin "1") (pinfunction "1_1") (pintype "passive"))
      (node (ref "R226") (pin "2") (pinfunction "2_2") (pintype "passive"))
    )
    (net (code "45") (name "/EEM2_5_P") (class "Default")
      (node (ref "J3") (pin "17") (pinfunction "17_17") (pintype "bidirectional"))
      (node (ref "R140") (pin "2") (pinfunction "2_2") (pintype "passive"))
      (node (ref "R227") (pin "2") (pinfunction "2_2") (pintype "passive"))
    )
    (net (code "46") (name "/EEM2_6_N") (class "Default")
      (node (ref "J3") (pin "21") (pinfunction "21_21") (pintype "bidirectional"))
      (node (ref "R142") (pin "1") (pinfunction "1_1") (pintype "passive"))
      (node (ref "R228") (pin "2") (pinfunction "2_2") (pintype "passive"))
    )
    (net (code "47") (name "/EEM2_6_P") (class "Default")
      (node (ref "J3") (pin "20") (pinfunction "20_20") (pintype "bidirectional"))
      (node (ref "R142") (pin "2") (pinfunction "2_2") (pintype "passive"))
      (node (ref "R229") (pin "2") (pinfunction "2_2") (pintype "passive"))
    )
    (net (code "48") (name "/EEM2_7_N") (class "Default")
      (node (ref "J3") (pin "24") (pinfunction "24_24") (pintype "bidirectional"))
      (node (ref "R144") (pin "1") (pinfunction "1_1") (pintype "passive"))
      (node (ref "R230") (pin "2") (pinfunction "2_2") (pintype "passive"))
    )
    (net (code "49") (name "/EEM2_7_P") (class "Default")
      (node (ref "J3") (pin "23") (pinfunction "23_23") (pintype "bidirectional"))
      (node (ref "R144") (pin "2") (pinfunction "2_2") (pintype "passive"))
      (node (ref "R231") (pin "2") (pinfunction "2_2") (pintype "passive"))
    )
    (net (code "50") (name "/I2C0_SCL") (class "Default")
      (node (ref "J1") (pin "27") (pinfunction "27_27") (pintype "bidirectional"))
    )
    (net (code "51") (name "/I2C0_SDA") (class "Default")
      (node (ref "J1") (pin "26") (pinfunction "26_26") (pintype "bidirectional"))
    )
    (net (code "52") (name "/I2C1_SCL") (class "Default")
      (node (ref "J2") (pin "27") (pinfunction "27_27") (pintype "bidirectional"))
    )
    (net (code "53") (name "/I2C1_SDA") (class "Default")
      (node (ref "J2") (pin "26") (pinfunction "26_26") (pintype "bidirectional"))
    )
    (net (code "54") (name "/I2C2_SCL") (class "Default")
      (node (ref "J3") (pin "27") (pinfunction "27_27") (pintype "bidirectional"))
    )
    (net (code "55") (name "/I2C2_SDA") (class "Default")
      (node (ref "J3") (pin "26") (pinfunction "26_26") (pintype "bidirectional"))
    )
    (net (code "56") (name "/I2C_RESET") (class "Default")
      (node (ref "U1") (pin "B2") (pinfunction "IOL_1B_B2") (pintype "bidirectional"))
    )
    (net (code "57") (name "/IOL_1A") (class "Default")
      (node (ref "TP10") (pin "1") (pintype "passive"))
      (node (ref "U1") (pin "E4") (pinfunction "IOL_1A_E4") (pintype "bidirectional"))
    )
    (net (code "58") (name "/IOL_9B") (class "Default")
      (node (ref "TP11") (pin "1") (pintype "passive"))
      (node (ref "U1") (pin "F2") (pinfunction "IOL_9B_F2") (pintype "bidirectional"))
    )
    (net (code "59") (name "/USR_LED") (class "Default")
      (node (ref "U1") (pin "H3") (pinfunction "IOL_9A_H3") (pintype "bidirectional"))
    )
    (net (code "61") (name "GND") (class "Default")
      (node (ref "J1") (pin "1") (pinfunction "1_1") (pintype "bidirectional"))
      (node (ref "J1") (pin "10") (pinfunction "10_10") (pintype "bidirectional"))
      (node (ref "J1") (pin "13") (pinfunction "13_13") (pintype "bidirectional"))
      (node (ref "J1") (pin "16") (pinfunction "16_16") (pintype "bidirectional"))
      (node (ref "J1") (pin "19") (pinfunction "19_19") (pintype "bidirectional"))
      (node (ref "J1") (pin "22") (pinfunction "22_22") (pintype "bidirectional"))
      (node (ref "J1") (pin "25") (pinfunction "25_25") (pintype "bidirectional"))
      (node (ref "J1") (pin "4") (pinfunction "4_4") (pintype "bidirectional"))
      (node (ref "J1") (pin "7") (pinfunction "7_7") (pintype "bidirectional"))
      (node (ref "J2") (pin "1") (pinfunction "1_1") (pintype "bidirectional"))
      (node (ref "J2") (pin "10") (pinfunction "10_10") (pintype "bidirectional"))
      (node (ref "J2") (pin "13") (pinfunction "13_13") (pintype "bidirectional"))
      (node (ref "J2") (pin "16") (pinfunction "16_16") (pintype "bidirectional"))
      (node (ref "J2") (pin "19") (pinfunction "19_19") (pintype "bidirectional"))
      (node (ref "J2") (pin "22") (pinfunction "22_22") (pintype "bidirectional"))
      (node (ref "J2") (pin "25") (pinfunction "25_25") (pintype "bidirectional"))
      (node (ref "J2") (pin "4") (pinfunction "4_4") (pintype "bidirectional"))
      (node (ref "J2") (pin "7") (pinfunction "7_7") (pintype "bidirectional"))
      (node (ref "J3") (pin "1") (pinfunction "1_1") (pintype "bidirectional"))
      (node (ref "J3") (pin "10") (pinfunction "10_10") (pintype "bidirectional"))
      (node (ref "J3") (pin "13") (pinfunction "13_13") (pintype "bidirectional"))
      (node (ref "J3") (pin "16") (pinfunction "16_16") (pintype "bidirectional"))
      (node (ref "J3") (pin "19") (pinfunction "19_19") (pintype "bidirectional"))
      (node (ref "J3") (pin "22") (pinfunction "22_22") (pintype "bidirectional"))
      (node (ref "J3") (pin "25") (pinfunction "25_25") (pintype "bidirectional"))
      (node (ref "J3") (pin "4") (pinfunction "4_4") (pintype "bidirectional"))
      (node (ref "J3") (pin "7") (pinfunction "7_7") (pintype "bidirectional"))
    )
    (net (code "62") (name "Net-(U1D-IOL_2A)") (class "Default")
      (node (ref "R178") (pin "1") (pinfunction "1_1") (pintype "passive"))
      (node (ref "U1") (pin "F5") (pinfunction "IOL_2A_F5") (pintype "bidirectional"))
    )
    (net (code "63") (name "Net-(U1D-IOL_2B)") (class "Default")
      (node (ref "R176") (pin "1") (pinfunction "1_1") (pintype "passive"))
      (node (ref "U1") (pin "B1") (pinfunction "IOL_2B_B1") (pintype "bidirectional"))
    )
    (net (code "64") (name "Net-(U1D-IOL_3A)") (class "Default")
      (node (ref "R182") (pin "1") (pinfunction "1_1") (pintype "passive"))
      (node (ref "U1") (pin "C1") (pinfunction "IOL_3A_C1") (pintype "bidirectional"))
    )
    (net (code "65") (name "Net-(U1D-IOL_3B)") (class "Default")
      (node (ref "R180") (pin "1") (pinfunction "1_1") (pintype "passive"))
      (node (ref "U1") (pin "C2") (pinfunction "IOL_3B_C2") (pintype "bidirectional"))
    )
    (net (code "66") (name "Net-(U1D-IOL_4A)") (class "Default")
      (node (ref "R186") (pin "1") (pinfunction "1_1") (pintype "passive"))
      (node (ref "U1") (pin "F4") (pinfunction "IOL_4A_F4") (pintype "bidirectional"))
    )
    (net (code "67") (name "Net-(U1D-IOL_4B)") (class "Default")
      (node (ref "R184") (pin "1") (pinfunction "1_1") (pintype "passive"))
      (node (ref "U1") (pin "D2") (pinfunction "IOL_4B_D2") (pintype "bidirectional"))
    )
    (net (code "68") (name "Net-(U1D-IOL_5A)") (class "Default")
      (node (ref "R189") (pin "1") (pinfunction "1_1") (pintype "passive"))
      (node (ref "U1") (pin "G5") (pinfunction "IOL_5A_G5") (pintype "bidirectional"))
    )
    (net (code "69") (name "Net-(U1D-IOL_5B)") (class "Default")
      (node (ref "R188") (pin "1") (pinfunction "1_1") (pintype "passive"))
      (node (ref "U1") (pin "D1") (pinfunction "IOL_5B_D1") (pintype "bidirectional"))
    )
    (net (code "70") (name "Net-(U1D-IOL_6A)") (class "Default")
      (node (ref "R191") (pin "1") (pinfunction "1_1") (pintype "passive"))
      (node (ref "U1") (pin "G4") (pinfunction "IOL_6A_G4") (pintype "bidirectional"))
    )
    (net (code "71") (name "Net-(U1D-IOL_6B)") (class "Default")
      (node (ref "R190") (pin "1") (pinfunction "1_1") (pintype "passive"))
      (node (ref "U1") (pin "E3") (pinfunction "IOL_6B_E3") (pintype "bidirectional"))
    )
    (net (code "72") (name "Net-(U1D-IOL_7A)") (class "Default")
      (node (ref "R193") (pin "1") (pinfunction "1_1") (pintype "passive"))
      (node (ref "U1") (pin "H5") (pinfunction "IOL_7A_H5") (pintype "bidirectional"))
    )
    (net (code "73") (name "Net-(U1D-IOL_7B)") (class "Default")
      (node (ref "R192") (pin "1") (pinfunction "1_1") (pintype "passive"))
      (node (ref "U1") (pin "E2") (pinfunction "IOL_7B_E2") (pintype "bidirectional"))
    )
    (net (code "74") (name "Net-(U1D-IOL_8A)") (class "Default")
      (node (ref "R195") (pin "1") (pinfunction "1_1") (pintype "passive"))
      (node (ref "U1") (pin "G3") (pinfunction "IOL_8A_G3") (pintype "bidirectional"))
    )
    (net (code "75") (name "Net-(U1D-IOL_8B)") (class "Default")
      (node (ref "R194") (pin "1") (pinfunction "1_1") (pintype "passive"))
      (node (ref "U1") (pin "F3") (pinfunction "IOL_8B_F3") (pintype "bidirectional"))
    )
    (net (code "76") (name "Net-(U1D-IOL_10A)") (class "Default")
      (node (ref "R197") (pin "1") (pinfunction "1_1") (pintype "passive"))
      (node (ref "U1") (pin "H6") (pinfunction "IOL_10A_H6") (pintype "bidirectional"))
    )
    (net (code "77") (name "Net-(U1D-IOL_10B)") (class "Default")
      (node (ref "R196") (pin "1") (pinfunction "1_1") (pintype "passive"))
      (node (ref "U1") (pin "F1") (pinfunction "IOL_10B_F1") (pintype "bidirectional"))
    )
    (net (code "78") (name "Net-(U1D-IOL_11A)") (class "Default")
      (node (ref "R199") (pin "1") (pinfunction "1_1") (pintype "passive"))
      (node (ref "U1") (pin "H4") (pinfunction "IOL_11A_H4") (pintype "bidirectional"))
    )
    (net (code "79") (name "Net-(U1D-IOL_11B)") (class "Default")
      (node (ref "R198") (pin "1") (pinfunction "1_1") (pintype "passive"))
      (node (ref "U1") (pin "G2") (pinfunction "IOL_11B_G2") (pintype "bidirectional"))
    )
    (net (code "80") (name "Net-(U1D-IOL_12A)") (class "Default")
      (node (ref "R203") (pin "1") (pinfunction "1_1") (pintype "passive"))
      (node (ref "U1") (pin "J4") (pinfunction "IOL_12A_J4") (pintype "bidirectional"))
    )
    (net (code "81") (name "Net-(U1D-IOL_12B)") (class "Default")
      (node (ref "R200") (pin "1") (pinfunction "1_1") (pintype "passive"))
      (node (ref "U1") (pin "H2") (pinfunction "IOL_12B_H2") (pintype "bidirectional"))
    )
    (net (code "82") (name "Net-(U1D-IOL_13A)") (class "Default")
      (node (ref "R205") (pin "1") (pinfunction "1_1") (pintype "passive"))
      (node (ref "U1") (pin "J5") (pinfunction "IOL_13A_J5") (pintype "bidirectional"))
    )
    (net (code "83") (name "Net-(U1D-IOL_13B_GBIN7)") (class "Default")
      (node (ref "R204") (pin "1") (pinfunction "1_1") (pintype "passive"))
      (node (ref "U1") (pin "G1") (pinfunction "IOL_13B_GBIN7_G1") (pintype "bidirectional"))
    )
    (net (code "84") (name "Net-(U1D-IOL_14A_GBIN6)") (class "Default")
      (node (ref "R207") (pin "1") (pinfunction "1_1") (pintype "passive"))
      (node (ref "U1") (pin "J3") (pinfunction "IOL_14A_GBIN6_J3") (pintype "bidirectional"))
    )
    (net (code "85") (name "Net-(U1D-IOL_14B)") (class "Default")
      (node (ref "R206") (pin "1") (pinfunction "1_1") (pintype "passive"))
      (node (ref "U1") (pin "H1") (pinfunction "IOL_14B_H1") (pintype "bidirectional"))
    )
    (net (code "86") (name "Net-(U1D-IOL_15A)") (class "Default")
      (node (ref "R209") (pin "1") (pinfunction "1_1") (pintype "passive"))
      (node (ref "U1") (pin "J2") (pinfunction "IOL_15A_J2") (pintype "bidirectional"))
    )
    (net (code "87") (name "Net-(U1D-IOL_15B)") (class "Default")
      (node (ref "R208") (pin "1") (pinfunction "1_1") (pintype "passive"))
      (node (ref "U1") (pin "J1") (pinfunction "IOL_15B_J1") (pintype "bidirectional"))
    )
    (net (code "88") (name "Net-(U1D-IOL_16A)") (class "Default")
      (node (ref "R211") (pin "1") (pinfunction "1_1") (pintype "passive"))
      (node (ref "U1") (pin "K1") (pinfunction "IOL_16A_K1") (pintype "bidirectional"))
    )
    (net (code "89") (name "Net-(U1D-IOL_16B)") (class "Default")
      (node (ref "R210") (pin "1") (pinfunction "1_1") (pintype "passive"))
      (node (ref "U1") (pin "K3") (pinfunction "IOL_16B_K3") (pintype "bidirectional"))
    )
    (net (code "90") (name "Net-(U1D-IOL_17A)") (class "Default")
      (node (ref "R213") (pin "1") (pinfunction "1_1") (pintype "passive"))
      (node (ref "U1") (pin "L4") (pinfunction "IOL_17A_L4") (pintype "bidirectional"))
    )
    (net (code "91") (name "Net-(U1D-IOL_17B)") (class "Default")
      (node (ref "R212") (pin "1") (pinfunction "1_1") (pintype "passive"))
      (node (ref "U1") (pin "L1") (pinfunction "IOL_17B_L1") (pintype "bidirectional"))
    )
    (net (code "92") (name "Net-(U1D-IOL_18A)") (class "Default")
      (node (ref "R215") (pin "1") (pinfunction "1_1") (pintype "passive"))
      (node (ref "U1") (pin "K4") (pinfunction "IOL_18A_K4") (pintype "bidirectional"))
    )
    (net (code "93") (name "Net-(U1D-IOL_18B)") (class "Default")
      (node (ref "R214") (pin "1") (pinfunction "1_1") (pintype "passive"))
      (node (ref "U1") (pin "M1") (pinfunction "IOL_18B_M1") (pintype "bidirectional"))
    )
    (net (code "94") (name "Net-(U1D-IOL_19A)") (class "Default")
      (node (ref "R217") (pin "1") (pinfunction "1_1") (pintype "passive"))
      (node (ref "U1") (pin "L6") (pinfunction "IOL_19A_L6") (pintype "bidirectional"))
    )
    (net (code "95") (name "Net-(U1D-IOL_19B)") (class "Default")
      (node (ref "R216") (pin "1") (pinfunction "1_1") (pintype "passive"))
      (node (ref "U1") (pin "L3") (pinfunction "IOL_19B_L3") (pintype "bidirectional"))
    )
    (net (code "96") (name "Net-(U1D-IOL_20A)") (class "Default")
      (node (ref "R219") (pin "1") (pinfunction "1_1") (pintype "passive"))
      (node (ref "U1") (pin "K5") (pinfunction "IOL_20A_K5") (pintype "bidirectional"))
    )
    (net (code "97") (name "Net-(U1D-IOL_20B)") (class "Default")
      (node (ref "R218") (pin "1") (pinfunction "1_1") (pintype "passive"))
      (node (ref "U1") (pin "M2") (pinfunction "IOL_20B_M2") (pintype "bidirectional"))
    )
    (net (code "98") (name "Net-(U1D-IOL_21A)") (class "Default")
      (node (ref "R221") (pin "1") (pinfunction "1_1") (pintype "passive"))
      (node (ref "U1") (pin "L7") (pinfunction "IOL_21A_L7") (pintype "bidirectional"))
    )
    (net (code "99") (name "Net-(U1D-IOL_21B)") (class "Default")
      (node (ref "R220") (pin "1") (pinfunction "1_1") (pintype "passive"))
      (node (ref "U1") (pin "N2") (pinfunction "IOL_21B_N2") (pintype "bidirectional"))
    )
    (net (code "100") (name "Net-(U1D-IOL_22A)") (class "Default")
      (node (ref "R223") (pin "1") (pinfunction "1_1") (pintype "passive"))
      (node (ref "U1") (pin "M6") (pinfunction "IOL_22A_M6") (pintype "bidirectional"))
    )
    (net (code "101") (name "Net-(U1D-IOL_22B)") (class "Default")
      (node (ref "R222") (pin "1") (pinfunction "1_1") (pintype "passive"))
      (node (ref "U1") (pin "M3") (pinfunction "IOL_22B_M3") (pintype "bidirectional"))
    )
    (net (code "102") (name "Net-(U1D-IOL_23A)") (class "Default")
      (node (ref "R225") (pin "1") (pinfunction "1_1") (pintype "passive"))
      (node (ref "U1") (pin "L5") (pinfunction "IOL_23A_L5") (pintype "bidirectional"))
    )
    (net (code "103") (name "Net-(U1D-IOL_23B)") (class "Default")
      (node (ref "R224") (pin "1") (pinfunction "1_1") (pintype "passive"))
      (node (ref "U1") (pin "N3") (pinfunction "IOL_23B_N3") (pintype "bidirectional"))
    )
    (net (code "104") (name "Net-(U1D-IOL_24A)") (class "Default")
      (node (ref "R227") (pin "1") (pinfunction "1_1") (pintype "passive"))
      (node (ref "U1") (pin "P1") (pinfunction "IOL_24A_P1") (pintype "bidirectional"))
    )
    (net (code "105") (name "Net-(U1D-IOL_24B)") (class "Default")
      (node (ref "R226") (pin "1") (pinfunction "1_1") (pintype "passive"))
      (node (ref "U1") (pin "M4") (pinfunction "IOL_24B_M4") (pintype "bidirectional"))
    )
    (net (code "106") (name "Net-(U1D-IOL_25A)") (class "Default")
      (node (ref "R229") (pin "1") (pinfunction "1_1") (pintype "passive"))
      (node (ref "U1") (pin "P2") (pinfunction "IOL_25A_P2") (pintype "bidirectional"))
    )
    (net (code "107") (name "Net-(U1D-IOL_25B)") (class "Default")
      (node (ref "R228") (pin "1") (pinfunction "1_1") (pintype "passive"))
      (node (ref "U1") (pin "M5") (pinfunction "IOL_25B_M5") (pintype "bidirectional"))
    )
    (net (code "108") (name "Net-(U1D-IOL_26A)") (class "Default")
      (node (ref "R231") (pin "1") (pinfunction "1_1") (pintype "passive"))
      (node (ref "U1") (pin "R1") (pinfunction "IOL_26A_R1") (pintype "bidirectional"))
    )
    (net (code "109") (name "Net-(U1D-IOL_26B)") (class "Default")
      (node (ref "R230") (pin "1") (pinfunction "1_1") (pintype "passive"))
      (node (ref "U1") (pin "N4") (pinfunction "IOL_26B_N4") (pintype "bidirectional"))
    )
    (net (code "110") (name "P3V3MP") (class "Default")
      (node (ref "J1") (pin "30") (pinfunction "30_30") (pintype "bidirectional"))
      (node (ref "J2") (pin "30") (pinfunction "30_30") (pintype "bidirectional"))
      (node (ref "J3") (pin "30") (pinfunction "30_30") (pintype "bidirectional"))
    )
    (net (code "111") (name "P12V0") (class "Default")
      (node (ref "J1") (pin "28") (pinfunction "28_28") (pintype "bidirectional"))
      (node (ref "J1") (pin "29") (pinfunction "29_29") (pintype "bidirectional"))
      (node (ref "J2") (pin "28") (pinfunction "28_28") (pintype "bidirectional"))
      (node (ref "J2") (pin "29") (pinfunction "29_29") (pintype "bidirectional"))
      (node (ref "J3") (pin "28") (pinfunction "28_28") (pintype "bidirectional"))
      (node (ref "J3") (pin "29") (pinfunction "29_29") (pintype "bidirectional"))
    )
  )
)
